# USB.net
KiCad netlist of a schematic drawn in Altium Designer
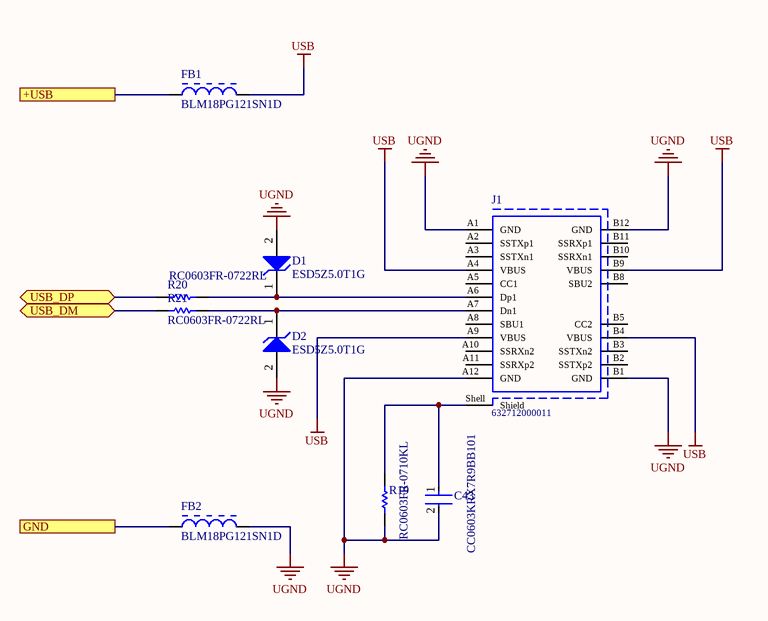
[diagram p0: USB.SchDoc]

(export (version "E")
  (design (tool "Eeschema 10.0.6"))
  (components
    (comp (ref "C43")
      (value "CC0603KRX7R9BB101")
      (footprint "FP-CC0603-DA-MFG")
      (description "CAP CER 100PF 50V X7R 0603")
      (fields
        (field (name "TOLERANCE") "0.1")
        (field (name "OCTOPART") "https://octopart.com/cc0603krx7r9bb101-yageo-42334526")
      )
      (libsource (lib "Altium Content Vault") (part "11868f565c42a9108669ba33697ecf6"))
    )
    (comp (ref "D1")
      (value "ESD5Z5.0T1G")
      (footprint "ONSC-SOD-523-2-502-01_V")
      (fields (field (name "MANUFACTURER") "On Semiconductor"))
      (libsource (lib "Altium Content Vault") (part "ONSC-K1A2-2"))
    )
    (comp (ref "D2")
      (value "ESD5Z5.0T1G")
      (footprint "ONSC-SOD-523-2-502-01_V")
      (fields (field (name "MANUFACTURER") "On Semiconductor"))
      (libsource (lib "Altium Content Vault") (part "ONSC-K1A2-2"))
    )
    (comp (ref "FB1")
      (value "BLM18PG121SN1D")
      (footprint "MURA-BLM18PG_KG-B25-CHIP-2_V1")
      (fields (field (name "MANUFACTURER") "Murata"))
      (libsource (lib "Altium Content Vault") (part "MURA-FB-2"))
    )
    (comp (ref "FB2")
      (value "BLM18PG121SN1D")
      (footprint "MURA-BLM18PG_KG-B25-CHIP-2_V1")
      (fields (field (name "MANUFACTURER") "Murata"))
      (libsource (lib "Altium Content Vault") (part "MURA-FB-2"))
    )
    (comp (ref "J1")
      (value "632712000011")
      (footprint "632712000011")
      (description "USB 3.1 Type C Plug WR-COM, Horizontal, SMT")
      (fields (field (name "MANUFACTURER") "Wurth Elektronik") (field (name "PUBLISHER") "WurthElektronik"))
      (libsource (lib "Altium Content Vault") (part "WE-632712000011"))
    )
    (comp (ref "R19")
      (value "RC0603FR-0710KL")
      (footprint "RESC1608X55X25ML10T15")
      (description "Chip Resistor, 10 KOhm, +/- 1%, 01 W, -55 to 155 degC, 0603 (1608 Metric), RoHS, Tape and Reel")
      (fields (field (name "MANUFACTURER") "Yageo") (field (name "TOLERANCE") "1%"))
      (libsource (lib "Altium Content Vault") (part "RES-2"))
    )
    (comp (ref "R20")
      (value "RC0603FR-0722RL")
      (footprint "RESC1608X55X25NL10T15")
      (description "Chip Resistor, 22 Ohm, +/- 1%, 0.1 W, -55 to 155 degC, 0603 (1608 Metric), RoHS, Tape and Reel")
      (libsource (lib "Altium Content Vault") (part "RES-2"))
    )
    (comp (ref "R21")
      (value "RC0603FR-0722RL")
      (footprint "RESC1608X55X25NL10T15")
      (description "Chip Resistor, 22 Ohm, +/- 1%, 0.1 W, -55 to 155 degC, 0603 (1608 Metric), RoHS, Tape and Reel")
      (libsource (lib "Altium Content Vault") (part "RES-2"))
    )
  )
  (nets
    (net (code "1") (name "/+USB") (class "Default")
      (node (ref "FB1") (pin "1") (pinfunction "1_1") (pintype "passive"))
    )
    (net (code "2") (name "/GND") (class "Default")
      (node (ref "FB2") (pin "1") (pinfunction "1_1") (pintype "passive"))
    )
    (net (code "3") (name "/USB_DM") (class "Default")
      (node (ref "R21") (pin "1") (pinfunction "1_1") (pintype "passive"))
    )
    (net (code "4") (name "/USB_DP") (class "Default")
      (node (ref "R20") (pin "1") (pinfunction "1_1") (pintype "passive"))
    )
    (net (code "5") (name "Net-(D1-K)") (class "Default")
      (node (ref "D1") (pin "1") (pinfunction "K_1") (pintype "passive"))
      (node (ref "J1") (pin "A6") (pinfunction "Dp1_A6") (pintype "passive"))
      (node (ref "R20") (pin "2") (pinfunction "2_2") (pintype "passive"))
    )
    (net (code "6") (name "Net-(D2-K)") (class "Default")
      (node (ref "D2") (pin "1") (pinfunction "K_1") (pintype "passive"))
      (node (ref "J1") (pin "A7") (pinfunction "Dn1_A7") (pintype "passive"))
      (node (ref "R21") (pin "2") (pinfunction "2_2") (pintype "passive"))
    )
    (net (code "7") (name "Net-(J1-Shield)") (class "Default")
      (node (ref "C43") (pin "1") (pinfunction "1_1") (pintype "passive"))
      (node (ref "J1") (pin "Shell") (pinfunction "Shield_Shell") (pintype "passive"))
      (node (ref "R19") (pin "1") (pinfunction "1_1") (pintype "passive"))
    )
    (net (code "8") (name "UGND") (class "Default")
      (node (ref "C43") (pin "2") (pinfunction "2_2") (pintype "passive"))
      (node (ref "D1") (pin "2") (pinfunction "A_2") (pintype "passive"))
      (node (ref "D2") (pin "2") (pinfunction "A_2") (pintype "passive"))
      (node (ref "FB2") (pin "2") (pinfunction "2_2") (pintype "passive"))
      (node (ref "J1") (pin "A1") (pinfunction "GND_A1") (pintype "passive"))
      (node (ref "J1") (pin "A12") (pinfunction "GND_A12") (pintype "passive"))
      (node (ref "J1") (pin "B1") (pinfunction "GND_B1") (pintype "passive"))
      (node (ref "J1") (pin "B12") (pinfunction "GND_B12") (pintype "passive"))
      (node (ref "R19") (pin "2") (pinfunction "2_2") (pintype "passive"))
    )
    (net (code "9") (name "USB") (class "Default")
      (node (ref "FB1") (pin "2") (pinfunction "2_2") (pintype "passive"))
      (node (ref "J1") (pin "A4") (pinfunction "VBUS_A4") (pintype "passive"))
      (node (ref "J1") (pin "A9") (pinfunction "VBUS_A9") (pintype "passive"))
      (node (ref "J1") (pin "B4") (pinfunction "VBUS_B4") (pintype "passive"))
      (node (ref "J1") (pin "B9") (pinfunction "VBUS_B9") (pintype "passive"))
    )
    (net (code "10") (name "unconnected-(J1-CC1-PadA5)") (class "Default")
      (node (ref "J1") (pin "A5") (pinfunction "CC1_A5") (pintype "passive"))
    )
    (net (code "11") (name "unconnected-(J1-CC2-PadB5)") (class "Default")
      (node (ref "J1") (pin "B5") (pinfunction "CC2_B5") (pintype "passive"))
    )
    (net (code "12") (name "unconnected-(J1-SBU1-PadA8)") (class "Default")
      (node (ref "J1") (pin "A8") (pinfunction "SBU1_A8") (pintype "passive"))
    )
    (net (code "13") (name "unconnected-(J1-SBU2-PadB8)") (class "Default")
      (node (ref "J1") (pin "B8") (pinfunction "SBU2_B8") (pintype "passive"))
    )
    (net (code "14") (name "unconnected-(J1-SSRXn1-PadB10)") (class "Default")
      (node (ref "J1") (pin "B10") (pinfunction "SSRXn1_B10") (pintype "passive"))
    )
    (net (code "15") (name "unconnected-(J1-SSRXn2-PadA10)") (class "Default")
      (node (ref "J1") (pin "A10") (pinfunction "SSRXn2_A10") (pintype "passive"))
    )
    (net (code "16") (name "unconnected-(J1-SSRXp1-PadB11)") (class "Default")
      (node (ref "J1") (pin "B11") (pinfunction "SSRXp1_B11") (pintype "passive"))
    )
    (net (code "17") (name "unconnected-(J1-SSRXp2-PadA11)") (class "Default")
      (node (ref "J1") (pin "A11") (pinfunction "SSRXp2_A11") (pintype "passive"))
    )
    (net (code "18") (name "unconnected-(J1-SSTXn1-PadA3)") (class "Default")
      (node (ref "J1") (pin "A3") (pinfunction "SSTXn1_A3") (pintype "passive"))
    )
    (net (code "19") (name "unconnected-(J1-SSTXn2-PadB3)") (class "Default")
      (node (ref "J1") (pin "B3") (pinfunction "SSTXn2_B3") (pintype "passive"))
    )
    (net (code "20") (name "unconnected-(J1-SSTXp1-PadA2)") (class "Default")
      (node (ref "J1") (pin "A2") (pinfunction "SSTXp1_A2") (pintype "passive"))
    )
    (net (code "21") (name "unconnected-(J1-SSTXp2-PadB2)") (class "Default")
      (node (ref "J1") (pin "B2") (pinfunction "SSTXp2_B2") (pintype "passive"))
    )
  )
)
